# USB_Type_C_Power_Controller.net
KiCad netlist of a schematic drawn in Altium Designer
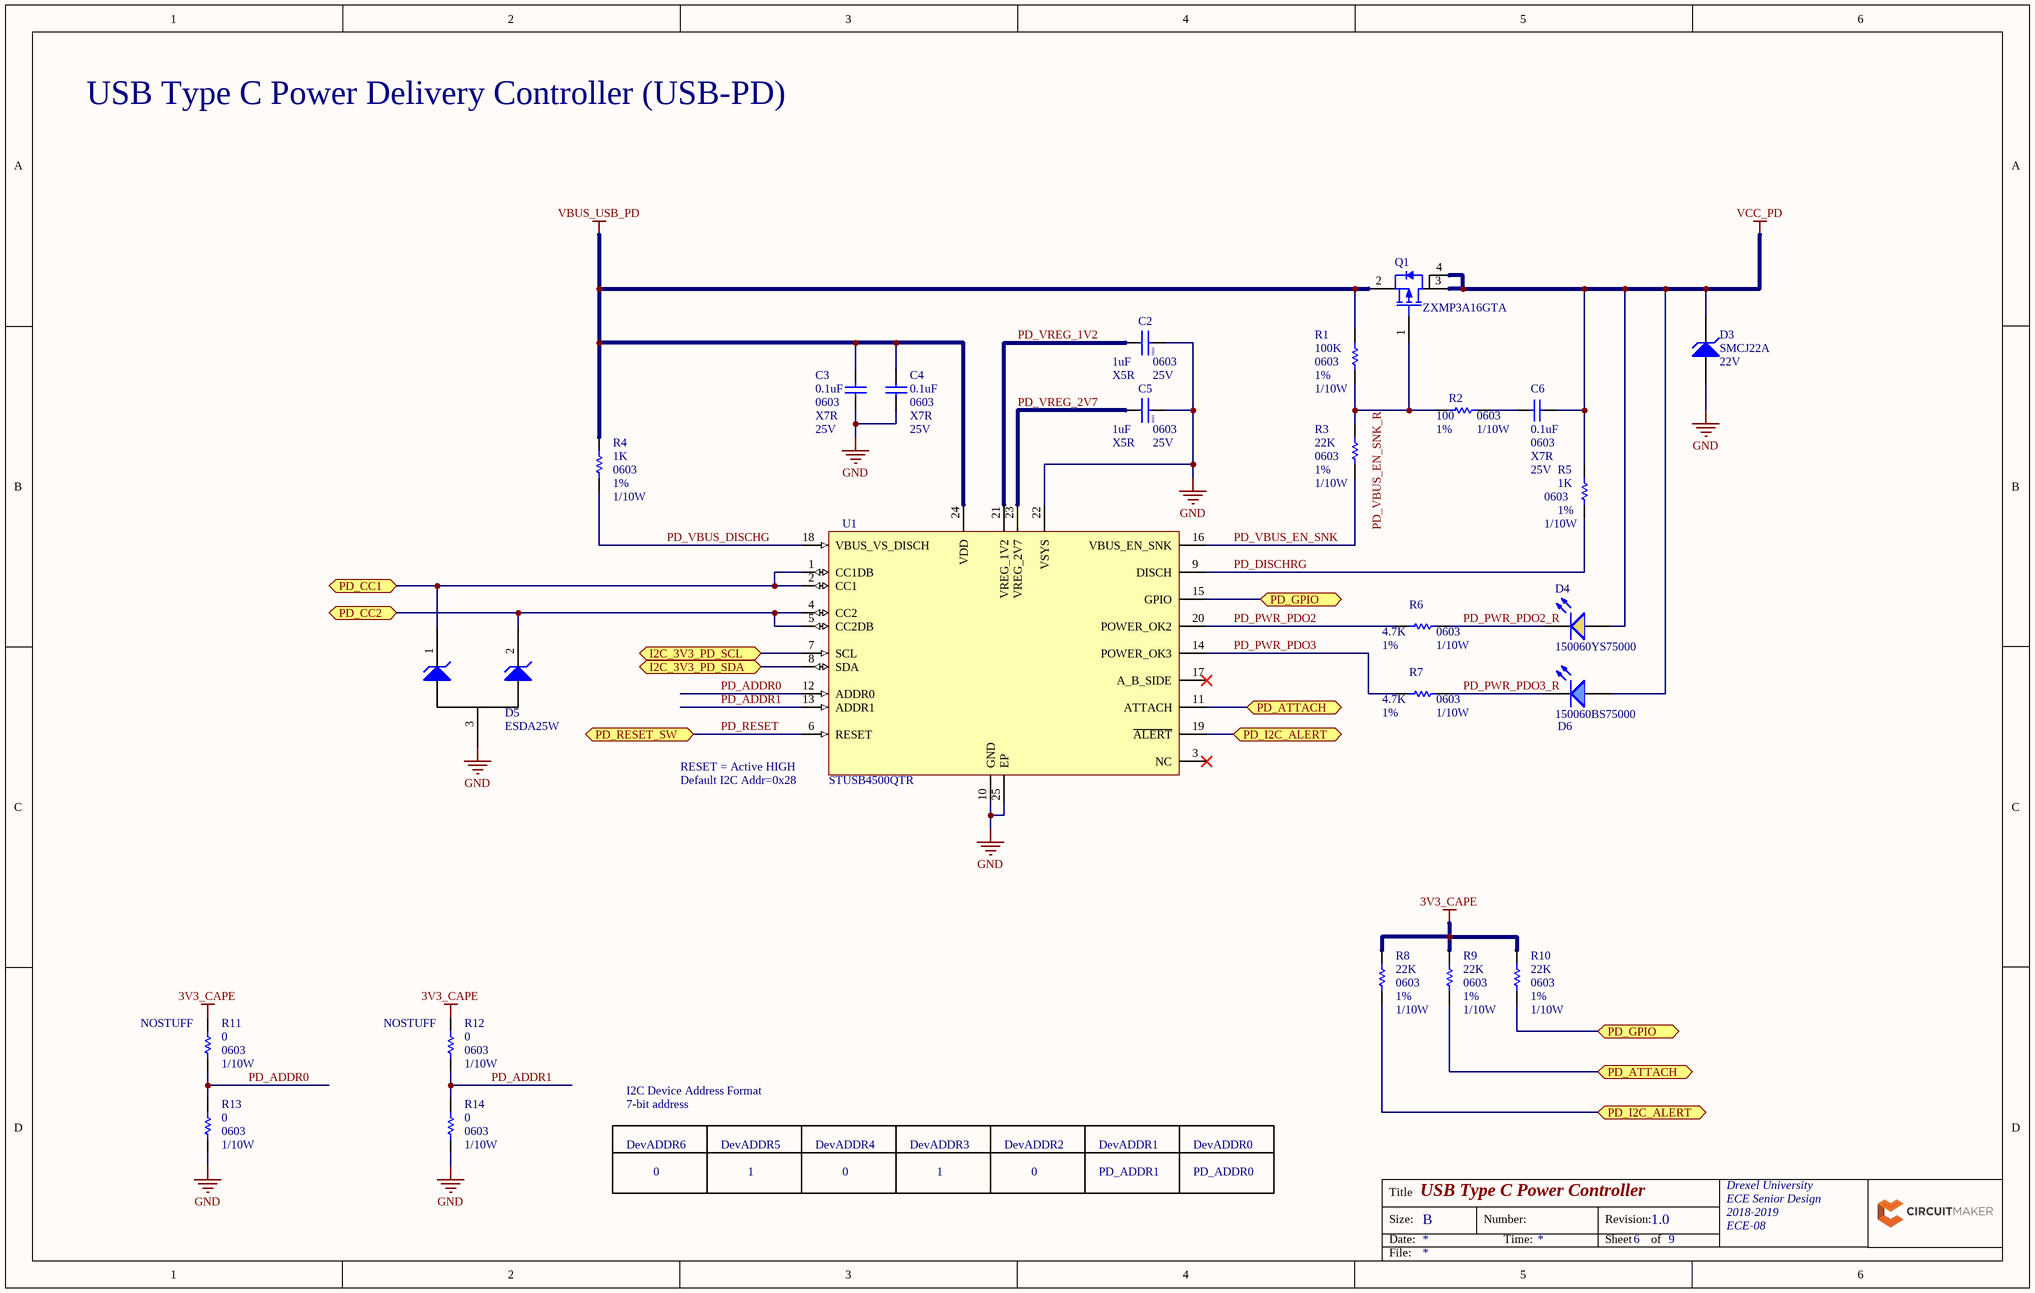
[diagram p0: USB Type C Power Controller.SchDoc]

(export (version "E")
  (design (tool "Eeschema 10.0.6"))
  (components
    (comp (ref "C2")
      (value "Taiyo Yuden TMK107BJ105KA-T")
      (footprint "PCB-bncvufzharetcg4gy1u6-1")
      (description "Cap Ceramic 1uF 25V X5R 10% SMD 0603 85°C Paper T/R")
      (fields
        (field (name "CASE/PACKAGE") "0603")
        (field (name "DIELECTRIC CHARACTERISTIC") "X5R")
        (field (name "CAPACITANCE") "1uF")
        (field (name "VOLTAGE RATING (DC)") "25V")
        (field (name "MANUFACTURER PART NUMBER") "TMK107BJ105KA-T")
      )
      (libsource (lib "CommunityVault") (part "CMP-ac4e65478e587389-1"))
    )
    (comp (ref "C3")
      (value "Würth Elektronik 885012206071")
      (footprint "PCB-8usp83j76ntw2xroyu3n-1")
      (description "Multilayer Ceramic Capacitor, WCAP-CSGP Series, 0.1 F, 10%, X7R, 25 V, 0603 [1608 Metric]")
      (fields
        (field (name "DIELECTRIC CHARACTERISTIC") "X7R")
        (field (name "VOLTAGE RATING (DC)") "25V")
        (field (name "CAPACITANCE") "0.1uF")
        (field (name "MANUFACTURER PART NUMBER") "885012206071")
        (field (name "PACKAGE") "0603")
      )
      (libsource (lib "CommunityVault") (part "CMP-034ac9768ab0dc8d-1"))
    )
    (comp (ref "C4")
      (value "Würth Elektronik 885012206071")
      (footprint "PCB-8usp83j76ntw2xroyu3n-1")
      (description "Multilayer Ceramic Capacitor, WCAP-CSGP Series, 0.1 F, 10%, X7R, 25 V, 0603 [1608 Metric]")
      (fields
        (field (name "DIELECTRIC CHARACTERISTIC") "X7R")
        (field (name "VOLTAGE RATING (DC)") "25V")
        (field (name "CAPACITANCE") "0.1uF")
        (field (name "MANUFACTURER PART NUMBER") "885012206071")
        (field (name "PACKAGE") "0603")
      )
      (libsource (lib "CommunityVault") (part "CMP-034ac9768ab0dc8d-1"))
    )
    (comp (ref "C5")
      (value "Taiyo Yuden TMK107BJ105KA-T")
      (footprint "PCB-bncvufzharetcg4gy1u6-1")
      (description "Cap Ceramic 1uF 25V X5R 10% SMD 0603 85°C Paper T/R")
      (fields
        (field (name "CASE/PACKAGE") "0603")
        (field (name "DIELECTRIC CHARACTERISTIC") "X5R")
        (field (name "CAPACITANCE") "1uF")
        (field (name "VOLTAGE RATING (DC)") "25V")
        (field (name "MANUFACTURER PART NUMBER") "TMK107BJ105KA-T")
      )
      (libsource (lib "CommunityVault") (part "CMP-ac4e65478e587389-1"))
    )
    (comp (ref "C6")
      (value "Würth Elektronik 885012206071")
      (footprint "PCB-8usp83j76ntw2xroyu3n-1")
      (description "Multilayer Ceramic Capacitor, WCAP-CSGP Series, 0.1 F, 10%, X7R, 25 V, 0603 [1608 Metric]")
      (fields
        (field (name "DIELECTRIC CHARACTERISTIC") "X7R")
        (field (name "VOLTAGE RATING (DC)") "25V")
        (field (name "CAPACITANCE") "0.1uF")
        (field (name "MANUFACTURER PART NUMBER") "885012206071")
        (field (name "PACKAGE") "0603")
      )
      (libsource (lib "CommunityVault") (part "CMP-034ac9768ab0dc8d-1"))
    )
    (comp (ref "D3")
      (value "SMCJ22A")
      (footprint "PCB-gk7qhtajnaxh6qo3xtq4-1")
      (description "SMCJ Series 35.5 V 1.5 kW Surface Mount Uni-Directional TVS Diode - DO-214AB")
      (fields (field (name "REVERSE VOLTAGE") "22V"))
      (libsource (lib "CommunityVault") (part "CMP-9cf25530e9434335-1"))
    )
    (comp (ref "D4")
      (value "150060YS75000")
      (footprint "PCB-pyamyqkabampf41w6k2s-1")
      (description "Standard LEDs - SMD WL-SMCW SMDMono TpVw Waterclr 0603 Yellow")
      (libsource (lib "CommunityVault") (part "SYM-fe0f36c1264421c8-1"))
    )
    (comp (ref "D5")
      (value "D Zener")
      (footprint "SOT65P210X110-3N")
      (description "ESD Suppressor TVS Uni-Dir 24V Automotive 3-Pin SOT-323 T/R")
      (fields (field (name "MANUFACTURER PART NUMBER") "ESDA25W"))
      (libsource (lib "CommunityVault") (part "CMP-6dd1a4de068db216-2"))
    )
    (comp (ref "D6")
      (value "150060BS75000")
      (footprint "PCB-q13q7q9xcpj9ke5g4s5g-1")
      (description "Standard LEDs - SMD WL-SMCW SMDMono TpVw Waterclr 0603 Blue")
      (libsource (lib "CommunityVault") (part "CMP-12518856-7"))
    )
    (comp (ref "Q1")
      (value "SYM-6957a0575e87b690-1")
      (footprint "SOT230P700X160-4N")
      (description "Trans MOSFET P-CH 30V 7.5A Automotive 4-Pin(3+Tab) SOT-223 T/R")
      (fields (field (name "MANUFACTURER PART NUMBER") "ZXMP3A16GTA"))
      (libsource (lib "CommunityVault") (part "CMP-6957a0575e87b690-4"))
    )
    (comp (ref "R1")
      (value "Res1")
      (footprint "PCB-js3e944hkesj3cskg8px-1")
      (description "Res Thick Film 0603 100K Ohm 1% 0.1W(1/10W) ±100ppm/C Pad SMD T/R")
      (fields
        (field (name "RESISTANCE") "100K")
        (field (name "POWER RATING") "1/10W")
        (field (name "PACKAGE") "0603")
        (field (name "TOLERANCE") "1%")
      )
      (libsource (lib "CommunityVault") (part "CMP-47e38e6423219824-1"))
    )
    (comp (ref "R2")
      (value "Stackpole Electronics RMCF0603FG100R")
      (footprint "PCB-85l72t2kcrpp9pohrqyw-1")
      (description "Res Thick Film 0603 100 Ohm 1% 0.1W(1/10W) ±100ppm/C Pad SMD Automotive T/R")
      (fields
        (field (name "MANUFACTURER PART NUMBER") "RMCF0603FG100R")
        (field (name "CASE/PACKAGE") "0603")
        (field (name "POWER RATING") "1/10W")
        (field (name "RESISTANCE") "100")
        (field (name "RESISTANCE TOLERANCE") "1%")
      )
      (libsource (lib "CommunityVault") (part "CMP-39aef181352de669-1"))
    )
    (comp (ref "R3")
      (value "Yageo RC0603FR-0722KL")
      (footprint "RESC1608X55X25LL10T15")
      (description "Chip Resistor, 22 KOhm, +/- 1%, 0.1 W, -55 to 155 degC, 0603 (1608 Metric), RoHS, Tape and Reel")
      (fields
        (field (name "RESISTANCE") "22K")
        (field (name "RESISTANCE TOLERANCE") "1%")
        (field (name "CASE/PACKAGE") "0603")
        (field (name "POWER RATING") "1/10W")
        (field (name "MANUFACTURER PART NUMBER") "RC0603FR-0722KL")
      )
      (libsource (lib "CommunityVault") (part "CMP-1853446-5"))
    )
    (comp (ref "R4")
      (value "Stackpole Electronics RMCF0603FT1K00")
      (footprint "PCB-rzdzs5ckhrcob8ss0hvn-1")
      (description "RMCF Series 0603 0.1 W 1 kOhm ±1 % ±100 ppm/°C SMT Thick Film Chip Resistor")
      (fields
        (field (name "CASE/PACKAGE") "0603")
        (field (name "POWER RATING") "1/10W")
        (field (name "MANUFACTURER PART NUMBER") "RMCF0603FT1K00")
        (field (name "RESISTANCE") "1K")
        (field (name "RESISTANCE TOLERANCE") "1%")
      )
      (libsource (lib "CommunityVault") (part "CMP-fdb3359cf2042274-2"))
    )
    (comp (ref "R5")
      (value "Stackpole Electronics RMCF0603FT1K00")
      (footprint "PCB-rzdzs5ckhrcob8ss0hvn-1")
      (description "RMCF Series 0603 0.1 W 1 kOhm ±1 % ±100 ppm/°C SMT Thick Film Chip Resistor")
      (fields
        (field (name "CASE/PACKAGE") "0603")
        (field (name "POWER RATING") "1/10W")
        (field (name "MANUFACTURER PART NUMBER") "RMCF0603FT1K00")
        (field (name "RESISTANCE") "1K")
        (field (name "RESISTANCE TOLERANCE") "1%")
      )
      (libsource (lib "CommunityVault") (part "CMP-fdb3359cf2042274-2"))
    )
    (comp (ref "R6")
      (value "4k7")
      (footprint "CAPC1608X90X35NL15T15")
      (description "Res Thick Film 0603 4.7K Ohm 1% 1/10W ±100ppm/°C Molded SMD SMD Paper Tape on Plastic Reel")
      (fields
        (field (name "RESISTANCE") "4.7K")
        (field (name "PACKAGE") "0603")
        (field (name "POWER RATING") "1/10W")
        (field (name "TOLERANCE") "1%")
      )
      (libsource (lib "CommunityVault") (part "CMP-3ca7f596181de360-9"))
    )
    (comp (ref "R7")
      (value "4k7")
      (footprint "CAPC1608X90X35NL15T15")
      (description "Res Thick Film 0603 4.7K Ohm 1% 1/10W ±100ppm/°C Molded SMD SMD Paper Tape on Plastic Reel")
      (fields
        (field (name "RESISTANCE") "4.7K")
        (field (name "PACKAGE") "0603")
        (field (name "POWER RATING") "1/10W")
        (field (name "TOLERANCE") "1%")
      )
      (libsource (lib "CommunityVault") (part "CMP-3ca7f596181de360-9"))
    )
    (comp (ref "R8")
      (value "Yageo RC0603FR-0722KL")
      (footprint "RESC1608X55X25LL10T15")
      (description "Chip Resistor, 22 KOhm, +/- 1%, 0.1 W, -55 to 155 degC, 0603 (1608 Metric), RoHS, Tape and Reel")
      (fields
        (field (name "RESISTANCE") "22K")
        (field (name "RESISTANCE TOLERANCE") "1%")
        (field (name "CASE/PACKAGE") "0603")
        (field (name "POWER RATING") "1/10W")
        (field (name "MANUFACTURER PART NUMBER") "RC0603FR-0722KL")
      )
      (libsource (lib "CommunityVault") (part "CMP-1853446-5"))
    )
    (comp (ref "R9")
      (value "Yageo RC0603FR-0722KL")
      (footprint "RESC1608X55X25LL10T15")
      (description "Chip Resistor, 22 KOhm, +/- 1%, 0.1 W, -55 to 155 degC, 0603 (1608 Metric), RoHS, Tape and Reel")
      (fields
        (field (name "RESISTANCE") "22K")
        (field (name "RESISTANCE TOLERANCE") "1%")
        (field (name "CASE/PACKAGE") "0603")
        (field (name "POWER RATING") "1/10W")
        (field (name "MANUFACTURER PART NUMBER") "RC0603FR-0722KL")
      )
      (libsource (lib "CommunityVault") (part "CMP-1853446-5"))
    )
    (comp (ref "R10")
      (value "Yageo RC0603FR-0722KL")
      (footprint "RESC1608X55X25LL10T15")
      (description "Chip Resistor, 22 KOhm, +/- 1%, 0.1 W, -55 to 155 degC, 0603 (1608 Metric), RoHS, Tape and Reel")
      (fields
        (field (name "RESISTANCE") "22K")
        (field (name "RESISTANCE TOLERANCE") "1%")
        (field (name "CASE/PACKAGE") "0603")
        (field (name "POWER RATING") "1/10W")
        (field (name "MANUFACTURER PART NUMBER") "RC0603FR-0722KL")
      )
      (libsource (lib "CommunityVault") (part "CMP-1853446-5"))
    )
    (comp (ref "R11")
      (value "Res1")
      (footprint "PCB-vghjuybc2rzv8513tm8h-1")
      (description "RES SMD 0 OHM JUMPER 1/10W 0603")
      (fields
        (field (name "SUPPLIER DEVICE PACKAGE") "0603")
        (field (name "MANUFACTURER PART NUMBER") "RC0603JR-070RL")
        (field (name "RESISTANCE") "0")
        (field (name "POWER") "1/10W")
        (field (name "ALTIUM_UNNAMED_1") "NOSTUFF")
      )
      (libsource (lib "CommunityVault") (part "CMP-536b9a7387ce8cac-9"))
    )
    (comp (ref "R12")
      (value "Res1")
      (footprint "PCB-vghjuybc2rzv8513tm8h-1")
      (description "RES SMD 0 OHM JUMPER 1/10W 0603")
      (fields
        (field (name "SUPPLIER DEVICE PACKAGE") "0603")
        (field (name "MANUFACTURER PART NUMBER") "RC0603JR-070RL")
        (field (name "RESISTANCE") "0")
        (field (name "POWER") "1/10W")
        (field (name "ALTIUM_UNNAMED_1") "NOSTUFF")
      )
      (libsource (lib "CommunityVault") (part "CMP-536b9a7387ce8cac-9"))
    )
    (comp (ref "R13")
      (value "Res1")
      (footprint "PCB-vghjuybc2rzv8513tm8h-1")
      (description "RES SMD 0 OHM JUMPER 1/10W 0603")
      (fields
        (field (name "SUPPLIER DEVICE PACKAGE") "0603")
        (field (name "MANUFACTURER PART NUMBER") "RC0603JR-070RL")
        (field (name "RESISTANCE") "0")
        (field (name "POWER") "1/10W")
      )
      (libsource (lib "CommunityVault") (part "CMP-536b9a7387ce8cac-9"))
    )
    (comp (ref "R14")
      (value "Res1")
      (footprint "PCB-vghjuybc2rzv8513tm8h-1")
      (description "RES SMD 0 OHM JUMPER 1/10W 0603")
      (fields
        (field (name "SUPPLIER DEVICE PACKAGE") "0603")
        (field (name "MANUFACTURER PART NUMBER") "RC0603JR-070RL")
        (field (name "RESISTANCE") "0")
        (field (name "POWER") "1/10W")
      )
      (libsource (lib "CommunityVault") (part "CMP-536b9a7387ce8cac-9"))
    )
    (comp (ref "U1")
      (value "STUSB4500QTR")
      (footprint "PCB-xnkkl1130v2ws1vguio4-1")
      (description "USB Type C and PD Sink Controller USB1.0/USB1.2/USB2.0/USB3.0 24-Pin QFN EP T/R")
      (libsource (lib "CommunityVault") (part "CMP-366efa1c2a7ce9a9-7"))
    )
  )
  (nets
    (net (code "1") (name "/I2C_3V3_PD_SCL") (class "Default")
      (node (ref "U1") (pin "7") (pinfunction "SCL_7") (pintype "input"))
    )
    (net (code "2") (name "/I2C_3V3_PD_SDA") (class "Default")
      (node (ref "U1") (pin "8") (pinfunction "SDA_8") (pintype "bidirectional"))
    )
    (net (code "3") (name "/PD_ADDR0") (class "Default")
      (node (ref "R11") (pin "1") (pinfunction "1_1") (pintype "passive"))
      (node (ref "R13") (pin "2") (pinfunction "2_2") (pintype "passive"))
      (node (ref "U1") (pin "12") (pinfunction "ADDR0_12") (pintype "input"))
    )
    (net (code "4") (name "/PD_ADDR1") (class "Default")
      (node (ref "R12") (pin "1") (pinfunction "1_1") (pintype "passive"))
      (node (ref "R14") (pin "2") (pinfunction "2_2") (pintype "passive"))
      (node (ref "U1") (pin "13") (pinfunction "ADDR1_13") (pintype "input"))
    )
    (net (code "5") (name "/PD_ATTACH") (class "Default")
      (node (ref "R9") (pin "1") (pinfunction "1_1") (pintype "passive"))
      (node (ref "U1") (pin "11") (pinfunction "ATTACH_11") (pintype "open_collector"))
    )
    (net (code "6") (name "/PD_CC1") (class "Default")
      (node (ref "D5") (pin "1") (pinfunction "1_1") (pintype "passive"))
      (node (ref "U1") (pin "1") (pinfunction "CC1DB_1") (pintype "bidirectional"))
      (node (ref "U1") (pin "2") (pinfunction "CC1_2") (pintype "bidirectional"))
    )
    (net (code "7") (name "/PD_CC2") (class "Default")
      (node (ref "D5") (pin "2") (pinfunction "2_2") (pintype "passive"))
      (node (ref "U1") (pin "4") (pinfunction "CC2_4") (pintype "bidirectional"))
      (node (ref "U1") (pin "5") (pinfunction "CC2DB_5") (pintype "bidirectional"))
    )
    (net (code "8") (name "/PD_DISCHRG") (class "Default")
      (node (ref "R5") (pin "1") (pinfunction "1_1") (pintype "passive"))
      (node (ref "U1") (pin "9") (pinfunction "DISCH_9") (pintype "open_collector"))
    )
    (net (code "9") (name "/PD_GPIO") (class "Default")
      (node (ref "R10") (pin "1") (pinfunction "1_1") (pintype "passive"))
      (node (ref "U1") (pin "15") (pinfunction "GPIO_15") (pintype "open_collector"))
    )
    (net (code "10") (name "/PD_I2C_ALERT") (class "Default")
      (node (ref "R8") (pin "1") (pinfunction "1_1") (pintype "passive"))
      (node (ref "U1") (pin "19") (pinfunction "~{ALERT}_19") (pintype "open_collector"))
    )
    (net (code "11") (name "/PD_PWR_PDO2") (class "Default")
      (node (ref "R6") (pin "1") (pinfunction "1_1") (pintype "passive"))
      (node (ref "U1") (pin "20") (pinfunction "POWER_OK2_20") (pintype "open_collector"))
    )
    (net (code "12") (name "/PD_PWR_PDO2_R") (class "Default")
      (node (ref "D4") (pin "1") (pinfunction "K_1") (pintype "passive"))
      (node (ref "R6") (pin "2") (pinfunction "2_2") (pintype "passive"))
    )
    (net (code "13") (name "/PD_PWR_PDO3") (class "Default")
      (node (ref "R7") (pin "1") (pinfunction "1_1") (pintype "passive"))
      (node (ref "U1") (pin "14") (pinfunction "POWER_OK3_14") (pintype "open_collector"))
    )
    (net (code "14") (name "/PD_PWR_PDO3_R") (class "Default")
      (node (ref "D6") (pin "1") (pinfunction "K_1") (pintype "passive"))
      (node (ref "R7") (pin "2") (pinfunction "2_2") (pintype "passive"))
    )
    (net (code "15") (name "/PD_RESET") (class "Default")
      (node (ref "U1") (pin "6") (pinfunction "RESET_6") (pintype "input"))
    )
    (net (code "16") (name "/PD_VBUS_DISCHG") (class "Default")
      (node (ref "R4") (pin "1") (pinfunction "1_1") (pintype "passive"))
      (node (ref "U1") (pin "18") (pinfunction "VBUS_VS_DISCH_18") (pintype "input"))
    )
    (net (code "17") (name "/PD_VBUS_EN_SNK") (class "Default")
      (node (ref "R3") (pin "1") (pinfunction "1_1") (pintype "passive"))
      (node (ref "U1") (pin "16") (pinfunction "VBUS_EN_SNK_16") (pintype "open_collector"))
    )
    (net (code "18") (name "/PD_VBUS_EN_SNK_R") (class "Default")
      (node (ref "Q1") (pin "1") (pinfunction "G_1") (pintype "passive"))
      (node (ref "R1") (pin "1") (pinfunction "1_1") (pintype "passive"))
      (node (ref "R2") (pin "1") (pinfunction "1_1") (pintype "passive"))
      (node (ref "R3") (pin "2") (pinfunction "2_2") (pintype "passive"))
    )
    (net (code "19") (name "/PD_VREG_1V2") (class "Default")
      (node (ref "C2") (pin "1") (pinfunction "1_1") (pintype "passive"))
      (node (ref "U1") (pin "21") (pinfunction "VREG_1V2_21") (pintype "power_in"))
    )
    (net (code "20") (name "/PD_VREG_2V7") (class "Default")
      (node (ref "C5") (pin "1") (pinfunction "1_1") (pintype "passive"))
      (node (ref "U1") (pin "23") (pinfunction "VREG_2V7_23") (pintype "power_in"))
    )
    (net (code "21") (name "3V3_CAPE") (class "Default")
      (node (ref "R10") (pin "2") (pinfunction "2_2") (pintype "passive"))
      (node (ref "R11") (pin "2") (pinfunction "2_2") (pintype "passive"))
      (node (ref "R12") (pin "2") (pinfunction "2_2") (pintype "passive"))
      (node (ref "R8") (pin "2") (pinfunction "2_2") (pintype "passive"))
      (node (ref "R9") (pin "2") (pinfunction "2_2") (pintype "passive"))
    )
    (net (code "22") (name "GND") (class "Default")
      (node (ref "C2") (pin "2") (pinfunction "2_2") (pintype "passive"))
      (node (ref "C3") (pin "1") (pinfunction "1_1") (pintype "passive"))
      (node (ref "C4") (pin "1") (pinfunction "1_1") (pintype "passive"))
      (node (ref "C5") (pin "2") (pinfunction "2_2") (pintype "passive"))
      (node (ref "D3") (pin "1") (pinfunction "A_1") (pintype "passive"))
      (node (ref "D5") (pin "3") (pinfunction "3_3") (pintype "passive"))
      (node (ref "R13") (pin "1") (pinfunction "1_1") (pintype "passive"))
      (node (ref "R14") (pin "1") (pinfunction "1_1") (pintype "passive"))
      (node (ref "U1") (pin "10") (pinfunction "GND_10") (pintype "power_in"))
      (node (ref "U1") (pin "22") (pinfunction "VSYS_22") (pintype "power_in"))
      (node (ref "U1") (pin "25") (pinfunction "EP_25") (pintype "power_in"))
    )
    (net (code "23") (name "Net-(C6-Pad1)") (class "Default")
      (node (ref "C6") (pin "1") (pinfunction "1_1") (pintype "passive"))
      (node (ref "R2") (pin "2") (pinfunction "2_2") (pintype "passive"))
    )
    (net (code "24") (name "VBUS_USB_PD") (class "Default")
      (node (ref "C3") (pin "2") (pinfunction "2_2") (pintype "passive"))
      (node (ref "C4") (pin "2") (pinfunction "2_2") (pintype "passive"))
      (node (ref "Q1") (pin "2") (pinfunction "S_2") (pintype "passive"))
      (node (ref "R1") (pin "2") (pinfunction "2_2") (pintype "passive"))
      (node (ref "R4") (pin "2") (pinfunction "2_2") (pintype "passive"))
      (node (ref "U1") (pin "24") (pinfunction "VDD_24") (pintype "power_in"))
    )
    (net (code "25") (name "VCC_PD") (class "Default")
      (node (ref "C6") (pin "2") (pinfunction "2_2") (pintype "passive"))
      (node (ref "D3") (pin "2") (pinfunction "K_2") (pintype "passive"))
      (node (ref "D4") (pin "2") (pinfunction "A_2") (pintype "passive"))
      (node (ref "D6") (pin "2") (pinfunction "A_2") (pintype "passive"))
      (node (ref "Q1") (pin "3") (pinfunction "D_3") (pintype "passive"))
      (node (ref "Q1") (pin "4") (pinfunction "4_4") (pintype "passive"))
      (node (ref "R5") (pin "2") (pinfunction "2_2") (pintype "passive"))
    )
    (net (code "26") (name "unconnected-(U1-A_B_SIDE-Pad17)") (class "Default")
      (node (ref "U1") (pin "17") (pinfunction "A_B_SIDE_17") (pintype "open_collector+no_connect"))
    )
    (net (code "27") (name "unconnected-(U1-NC-Pad3)") (class "Default")
      (node (ref "U1") (pin "3") (pinfunction "NC_3") (pintype "passive+no_connect"))
    )
  )
)
